# circuit.net
KiCad netlist of a schematic drawn in EAGLE
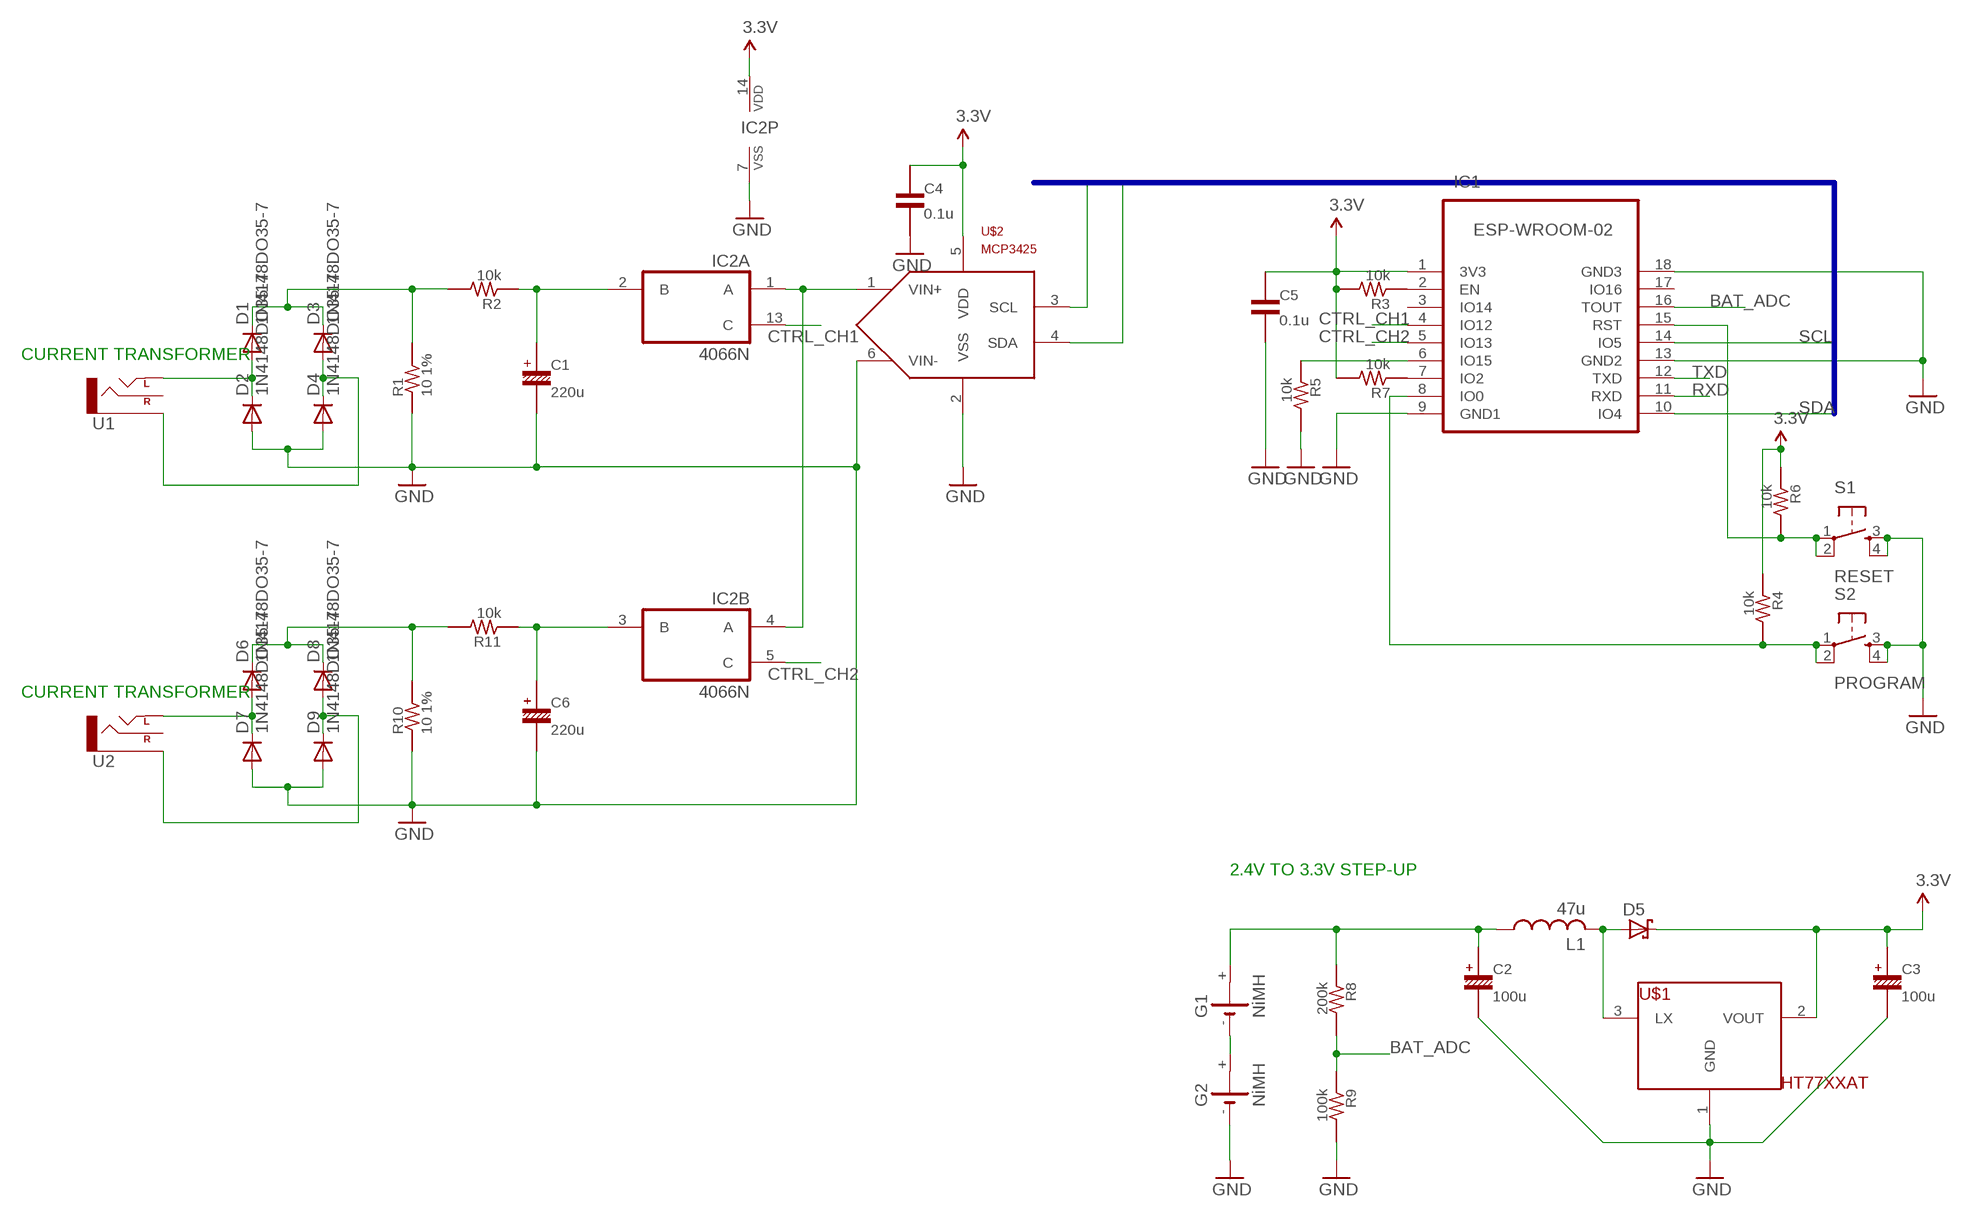
[diagram p0: schematic, sheet 1]

(export (version "E")
  (design (tool "Eeschema 10.0.6"))
  (components
    (comp (ref "C1")
      (value "220u")
      (footprint "eagle-import:16V-4-2.54")
      (libsource (lib "eagle-import") (part "CE-16V-04-2.54"))
    )
    (comp (ref "C2")
      (value "100u")
      (footprint "eagle-import:16V-6.3-5.08")
      (libsource (lib "eagle-import") (part "CE-16V-06.3-5.08"))
    )
    (comp (ref "C3")
      (value "100u")
      (footprint "eagle-import:16V-6.3-5.08")
      (libsource (lib "eagle-import") (part "CE-16V-06.3-5.08"))
    )
    (comp (ref "C4")
      (value "0.1u")
      (footprint "eagle-import:50-0302-2.54")
      (libsource (lib "eagle-import") (part "C-50V-0302-2.54"))
    )
    (comp (ref "C5")
      (value "0.1u")
      (footprint "eagle-import:50-0302-2.54")
      (libsource (lib "eagle-import") (part "C-50V-0302-2.54"))
    )
    (comp (ref "C6")
      (value "220u")
      (footprint "eagle-import:16V-4-2.54")
      (libsource (lib "eagle-import") (part "CE-16V-04-2.54"))
    )
    (comp (ref "D1")
      (value "1N4148DO35-7")
      (footprint "eagle-import:DO35-7")
      (libsource (lib "eagle-import") (part "1N4148DO35-7"))
    )
    (comp (ref "D2")
      (value "1N4148DO35-7")
      (footprint "eagle-import:DO35-7")
      (libsource (lib "eagle-import") (part "1N4148DO35-7"))
    )
    (comp (ref "D3")
      (value "1N4148DO35-7")
      (footprint "eagle-import:DO35-7")
      (libsource (lib "eagle-import") (part "1N4148DO35-7"))
    )
    (comp (ref "D4")
      (value "1N4148DO35-7")
      (footprint "eagle-import:DO35-7")
      (libsource (lib "eagle-import") (part "1N4148DO35-7"))
    )
    (comp (ref "D5")
      (value "SCHOTTKY-DIODEDO35-7")
      (footprint "eagle-import:DO35-7")
      (libsource (lib "eagle-import") (part "SCHOTTKY-DIODEDO35-7"))
    )
    (comp (ref "D6")
      (value "1N4148DO35-7")
      (footprint "eagle-import:DO35-7")
      (libsource (lib "eagle-import") (part "1N4148DO35-7"))
    )
    (comp (ref "D7")
      (value "1N4148DO35-7")
      (footprint "eagle-import:DO35-7")
      (libsource (lib "eagle-import") (part "1N4148DO35-7"))
    )
    (comp (ref "D8")
      (value "1N4148DO35-7")
      (footprint "eagle-import:DO35-7")
      (libsource (lib "eagle-import") (part "1N4148DO35-7"))
    )
    (comp (ref "D9")
      (value "1N4148DO35-7")
      (footprint "eagle-import:DO35-7")
      (libsource (lib "eagle-import") (part "1N4148DO35-7"))
    )
    (comp (ref "G1")
      (value "NiMH")
      (footprint "eagle-import:CRAA")
      (libsource (lib "eagle-import") (part "CRAA"))
    )
    (comp (ref "G2")
      (value "NiMH")
      (footprint "eagle-import:CRAA")
      (libsource (lib "eagle-import") (part "CRAA"))
    )
    (comp (ref "IC1")
      (value "ESP-WROOM-02")
      (footprint "eagle-import:ESP-WROOM-02")
      (libsource (lib "eagle-import") (part "ESP-WROOM-02"))
    )
    (comp (ref "IC2")
      (value "4066N")
      (footprint "eagle-import:DIL14")
      (libsource (lib "eagle-import") (part "4066N"))
    )
    (comp (ref "L1")
      (value "47u")
      (footprint "eagle-import:6000-XXXX-RC")
      (libsource (lib "eagle-import") (part "L-US6000-XXX-RC"))
    )
    (comp (ref "R1")
      (value "10 1%")
      (footprint "eagle-import:1_4W-7.62H")
      (libsource (lib "eagle-import") (part "R-1/4W-07.62"))
    )
    (comp (ref "R2")
      (value "10k")
      (footprint "eagle-import:1_4W-7.62H")
      (libsource (lib "eagle-import") (part "R-1/4W-07.62"))
    )
    (comp (ref "R3")
      (value "10k")
      (footprint "eagle-import:1_4W-7.62H")
      (libsource (lib "eagle-import") (part "R-1/4W-07.62"))
    )
    (comp (ref "R4")
      (value "10k")
      (footprint "eagle-import:1_4W-7.62H")
      (libsource (lib "eagle-import") (part "R-1/4W-07.62"))
    )
    (comp (ref "R5")
      (value "10k")
      (footprint "eagle-import:1_4W-7.62H")
      (libsource (lib "eagle-import") (part "R-1/4W-07.62"))
    )
    (comp (ref "R6")
      (value "10k")
      (footprint "eagle-import:1_4W-7.62H")
      (libsource (lib "eagle-import") (part "R-1/4W-07.62"))
    )
    (comp (ref "R7")
      (value "10k")
      (footprint "eagle-import:1_4W-7.62H")
      (libsource (lib "eagle-import") (part "R-1/4W-07.62"))
    )
    (comp (ref "R8")
      (value "200k")
      (footprint "eagle-import:1_4W-7.62H")
      (libsource (lib "eagle-import") (part "R-1/4W-07.62"))
    )
    (comp (ref "R9")
      (value "100k")
      (footprint "eagle-import:1_4W-7.62H")
      (libsource (lib "eagle-import") (part "R-1/4W-07.62"))
    )
    (comp (ref "R10")
      (value "10 1%")
      (footprint "eagle-import:1_4W-7.62H")
      (libsource (lib "eagle-import") (part "R-1/4W-07.62"))
    )
    (comp (ref "R11")
      (value "10k")
      (footprint "eagle-import:1_4W-7.62H")
      (libsource (lib "eagle-import") (part "R-1/4W-07.62"))
    )
    (comp (ref "S1")
      (value "RESET")
      (footprint "eagle-import:TACTILE-PTH")
      (libsource (lib "eagle-import") (part "TAC_SWITCHPTH"))
    )
    (comp (ref "S2")
      (value "PROGRAM")
      (footprint "eagle-import:TACTILE-PTH")
      (libsource (lib "eagle-import") (part "TAC_SWITCHPTH"))
    )
    (comp (ref "U$1")
      (value "HT77XXAT")
      (footprint "eagle-import:TO-92")
      (libsource (lib "eagle-import") (part "HT77XXAT"))
    )
    (comp (ref "U$2")
      (value "MCP3425")
      (footprint "eagle-import:SOT-23-6")
      (libsource (lib "eagle-import") (part "MCP3425"))
    )
    (comp (ref "U1")
      (value "AUDIO-JACK2.5MM")
      (footprint "eagle-import:STEREOJACK2.5MM_STEREOJACK2.5MM")
      (libsource (lib "eagle-import") (part "AUDIO-JACK2.5MM"))
    )
    (comp (ref "U2")
      (value "AUDIO-JACK2.5MM")
      (footprint "eagle-import:STEREOJACK2.5MM_STEREOJACK2.5MM")
      (libsource (lib "eagle-import") (part "AUDIO-JACK2.5MM"))
    )
  )
  (nets
    (net (code "1") (name "/BAT_ADC") (class "Default")
      (node (ref "IC1") (pin "16") (pinfunction "TOUT_16") (pintype "bidirectional"))
      (node (ref "R8") (pin "PAD2") (pinfunction "2_PAD2") (pintype "passive"))
      (node (ref "R9") (pin "PAD1") (pinfunction "1_PAD1") (pintype "passive"))
    )
    (net (code "2") (name "/CTRL_CH1") (class "Default")
      (node (ref "IC1") (pin "4") (pinfunction "IO12_4") (pintype "bidirectional"))
      (node (ref "IC2") (pin "13") (pinfunction "C_13") (pintype "input"))
    )
    (net (code "3") (name "/CTRL_CH2") (class "Default")
      (node (ref "IC1") (pin "5") (pinfunction "IO13_5") (pintype "bidirectional"))
      (node (ref "IC2") (pin "5") (pinfunction "C_5") (pintype "input"))
    )
    (net (code "4") (name "/RXD") (class "Default")
      (node (ref "IC1") (pin "11") (pinfunction "RXD_11") (pintype "bidirectional"))
    )
    (net (code "5") (name "/SCL") (class "Default")
      (node (ref "IC1") (pin "14") (pinfunction "IO5_14") (pintype "open_collector"))
      (node (ref "U$2") (pin "3") (pinfunction "SCL_3") (pintype "bidirectional"))
    )
    (net (code "6") (name "/SDA") (class "Default")
      (node (ref "IC1") (pin "10") (pinfunction "IO4_10") (pintype "bidirectional"))
      (node (ref "U$2") (pin "4") (pinfunction "SDA_4") (pintype "bidirectional"))
    )
    (net (code "7") (name "/TXD") (class "Default")
      (node (ref "IC1") (pin "12") (pinfunction "TXD_12") (pintype "bidirectional"))
    )
    (net (code "8") (name "3.3V") (class "Default")
      (node (ref "C3") (pin "+") (pinfunction "+_+") (pintype "passive"))
      (node (ref "C4") (pin "PAD1") (pinfunction "1_PAD1") (pintype "passive"))
      (node (ref "C5") (pin "PAD1") (pinfunction "1_PAD1") (pintype "passive"))
      (node (ref "D5") (pin "C") (pinfunction "C_C") (pintype "passive"))
      (node (ref "IC1") (pin "1") (pinfunction "3V3_1") (pintype "power_in"))
      (node (ref "IC2") (pin "14") (pinfunction "VDD_14") (pintype "power_in"))
      (node (ref "R3") (pin "PAD2") (pinfunction "2_PAD2") (pintype "passive"))
      (node (ref "R4") (pin "PAD1") (pinfunction "1_PAD1") (pintype "passive"))
      (node (ref "R6") (pin "PAD1") (pinfunction "1_PAD1") (pintype "passive"))
      (node (ref "R7") (pin "PAD2") (pinfunction "2_PAD2") (pintype "passive"))
      (node (ref "U$1") (pin "2") (pinfunction "VOUT_2") (pintype "power_in"))
      (node (ref "U$2") (pin "5") (pinfunction "VDD_5") (pintype "power_in"))
    )
    (net (code "9") (name "GND") (class "Default")
      (node (ref "C1") (pin "-") (pinfunction "-_-") (pintype "passive"))
      (node (ref "C2") (pin "-") (pinfunction "-_-") (pintype "passive"))
      (node (ref "C3") (pin "-") (pinfunction "-_-") (pintype "passive"))
      (node (ref "C4") (pin "PAD2") (pinfunction "2_PAD2") (pintype "passive"))
      (node (ref "C5") (pin "PAD2") (pinfunction "2_PAD2") (pintype "passive"))
      (node (ref "C6") (pin "-") (pinfunction "-_-") (pintype "passive"))
      (node (ref "D2") (pin "A") (pinfunction "A_A") (pintype "passive"))
      (node (ref "D4") (pin "A") (pinfunction "A_A") (pintype "passive"))
      (node (ref "D7") (pin "A") (pinfunction "A_A") (pintype "passive"))
      (node (ref "D9") (pin "A") (pinfunction "A_A") (pintype "passive"))
      (node (ref "G2") (pin "-") (pinfunction "-_-") (pintype "passive"))
      (node (ref "IC1") (pin "13") (pinfunction "GND2_13") (pintype "power_in"))
      (node (ref "IC1") (pin "18") (pinfunction "GND3_18") (pintype "power_in"))
      (node (ref "IC1") (pin "9") (pinfunction "GND1_9") (pintype "power_in"))
      (node (ref "IC2") (pin "7") (pinfunction "VSS_7") (pintype "power_in"))
      (node (ref "R1") (pin "PAD1") (pinfunction "1_PAD1") (pintype "passive"))
      (node (ref "R10") (pin "PAD1") (pinfunction "1_PAD1") (pintype "passive"))
      (node (ref "R5") (pin "PAD2") (pinfunction "2_PAD2") (pintype "passive"))
      (node (ref "R9") (pin "PAD2") (pinfunction "2_PAD2") (pintype "passive"))
      (node (ref "S1") (pin "3") (pinfunction "3_3") (pintype "passive"))
      (node (ref "S1") (pin "4") (pinfunction "4_4") (pintype "passive"))
      (node (ref "S2") (pin "3") (pinfunction "3_3") (pintype "passive"))
      (node (ref "S2") (pin "4") (pinfunction "4_4") (pintype "passive"))
      (node (ref "U$1") (pin "1") (pinfunction "GND_1") (pintype "power_in"))
      (node (ref "U$2") (pin "2") (pinfunction "VSS_2") (pintype "power_in"))
      (node (ref "U$2") (pin "6") (pinfunction "VIN-_6") (pintype "input"))
    )
    (net (code "10") (name "Net-(G1-Pad-)") (class "Default")
      (node (ref "G1") (pin "-") (pinfunction "-_-") (pintype "passive"))
      (node (ref "G2") (pin "+") (pinfunction "+_+") (pintype "passive"))
    )
    (net (code "11") (name "Net-(IC1-EN)") (class "Default")
      (node (ref "IC1") (pin "2") (pinfunction "EN_2") (pintype "bidirectional"))
      (node (ref "R3") (pin "PAD1") (pinfunction "1_PAD1") (pintype "passive"))
    )
    (net (code "12") (name "Net-(IC1-IO0)") (class "Default")
      (node (ref "IC1") (pin "8") (pinfunction "IO0_8") (pintype "bidirectional"))
      (node (ref "R4") (pin "PAD2") (pinfunction "2_PAD2") (pintype "passive"))
      (node (ref "S2") (pin "1") (pinfunction "1_1") (pintype "passive"))
      (node (ref "S2") (pin "2") (pinfunction "2_2") (pintype "passive"))
    )
    (net (code "13") (name "Net-(IC1-IO2)") (class "Default")
      (node (ref "IC1") (pin "7") (pinfunction "IO2_7") (pintype "bidirectional"))
      (node (ref "R7") (pin "PAD1") (pinfunction "1_PAD1") (pintype "passive"))
    )
    (net (code "14") (name "Net-(IC1-IO15)") (class "Default")
      (node (ref "IC1") (pin "6") (pinfunction "IO15_6") (pintype "bidirectional"))
      (node (ref "R5") (pin "PAD1") (pinfunction "1_PAD1") (pintype "passive"))
    )
    (net (code "15") (name "Net-(IC1-RST)") (class "Default")
      (node (ref "IC1") (pin "15") (pinfunction "RST_15") (pintype "bidirectional"))
      (node (ref "R6") (pin "PAD2") (pinfunction "2_PAD2") (pintype "passive"))
      (node (ref "S1") (pin "1") (pinfunction "1_1") (pintype "passive"))
      (node (ref "S1") (pin "2") (pinfunction "2_2") (pintype "passive"))
    )
    (net (code "16") (name "Net-(IC2A-A)") (class "Default")
      (node (ref "IC2") (pin "1") (pinfunction "A_1") (pintype "tri_state"))
      (node (ref "IC2") (pin "4") (pinfunction "A_4") (pintype "tri_state"))
      (node (ref "U$2") (pin "1") (pinfunction "VIN+_1") (pintype "input"))
    )
    (net (code "17") (name "Net-(IC2A-B)") (class "Default")
      (node (ref "C1") (pin "+") (pinfunction "+_+") (pintype "passive"))
      (node (ref "IC2") (pin "2") (pinfunction "B_2") (pintype "tri_state"))
      (node (ref "R2") (pin "PAD1") (pinfunction "1_PAD1") (pintype "passive"))
    )
    (net (code "18") (name "Net-(IC2B-B)") (class "Default")
      (node (ref "C6") (pin "+") (pinfunction "+_+") (pintype "passive"))
      (node (ref "IC2") (pin "3") (pinfunction "B_3") (pintype "tri_state"))
      (node (ref "R11") (pin "PAD1") (pinfunction "1_PAD1") (pintype "passive"))
    )
    (net (code "19") (name "Net-(R1-2)") (class "Default")
      (node (ref "D1") (pin "C") (pinfunction "C_C") (pintype "passive"))
      (node (ref "D3") (pin "C") (pinfunction "C_C") (pintype "passive"))
      (node (ref "R1") (pin "PAD2") (pinfunction "2_PAD2") (pintype "passive"))
      (node (ref "R2") (pin "PAD2") (pinfunction "2_PAD2") (pintype "passive"))
    )
    (net (code "20") (name "Net-(R8-1)") (class "Default")
      (node (ref "C2") (pin "+") (pinfunction "+_+") (pintype "passive"))
      (node (ref "G1") (pin "+") (pinfunction "+_+") (pintype "passive"))
      (node (ref "L1") (pin "1") (pinfunction "1_1") (pintype "passive"))
      (node (ref "R8") (pin "PAD1") (pinfunction "1_PAD1") (pintype "passive"))
    )
    (net (code "21") (name "Net-(R10-2)") (class "Default")
      (node (ref "D6") (pin "C") (pinfunction "C_C") (pintype "passive"))
      (node (ref "D8") (pin "C") (pinfunction "C_C") (pintype "passive"))
      (node (ref "R10") (pin "PAD2") (pinfunction "2_PAD2") (pintype "passive"))
      (node (ref "R11") (pin "PAD2") (pinfunction "2_PAD2") (pintype "passive"))
    )
    (net (code "22") (name "Net-(U$1-LX)") (class "Default")
      (node (ref "D5") (pin "A") (pinfunction "A_A") (pintype "passive"))
      (node (ref "L1") (pin "2") (pinfunction "2_2") (pintype "passive"))
      (node (ref "U$1") (pin "3") (pinfunction "LX_3") (pintype "power_in"))
    )
    (net (code "23") (name "Net-(U1-LEFT)") (class "Default")
      (node (ref "D1") (pin "A") (pinfunction "A_A") (pintype "passive"))
      (node (ref "D2") (pin "C") (pinfunction "C_C") (pintype "passive"))
      (node (ref "U1") (pin "SHIELD") (pinfunction "LEFT_SHIELD") (pintype "bidirectional"))
    )
    (net (code "24") (name "Net-(U1-SLEEVE)") (class "Default")
      (node (ref "D3") (pin "A") (pinfunction "A_A") (pintype "passive"))
      (node (ref "D4") (pin "C") (pinfunction "C_C") (pintype "passive"))
      (node (ref "U1") (pin "RING1") (pinfunction "SLEEVE_RING1") (pintype "bidirectional"))
    )
    (net (code "25") (name "Net-(U2-LEFT)") (class "Default")
      (node (ref "D6") (pin "A") (pinfunction "A_A") (pintype "passive"))
      (node (ref "D7") (pin "C") (pinfunction "C_C") (pintype "passive"))
      (node (ref "U2") (pin "SHIELD") (pinfunction "LEFT_SHIELD") (pintype "bidirectional"))
    )
    (net (code "26") (name "Net-(U2-SLEEVE)") (class "Default")
      (node (ref "D8") (pin "A") (pinfunction "A_A") (pintype "passive"))
      (node (ref "D9") (pin "C") (pinfunction "C_C") (pintype "passive"))
      (node (ref "U2") (pin "RING1") (pinfunction "SLEEVE_RING1") (pintype "bidirectional"))
    )
    (net (code "27") (name "unconnected-(G1-+-Pad+@1)") (class "Default")
      (node (ref "G1") (pin "+@1") (pinfunction "+_+@1") (pintype "passive"))
    )
    (net (code "28") (name "unconnected-(G2-+-Pad+@1)") (class "Default")
      (node (ref "G2") (pin "+@1") (pinfunction "+_+@1") (pintype "passive"))
    )
    (net (code "29") (name "unconnected-(IC1-IO14-Pad3)") (class "Default")
      (node (ref "IC1") (pin "3") (pinfunction "IO14_3") (pintype "bidirectional"))
    )
    (net (code "30") (name "unconnected-(IC1-IO16-Pad17)") (class "Default")
      (node (ref "IC1") (pin "17") (pinfunction "IO16_17") (pintype "bidirectional"))
    )
    (net (code "31") (name "unconnected-(U1-RIGHT-PadTIP)") (class "Default")
      (node (ref "U1") (pin "TIP") (pinfunction "RIGHT_TIP") (pintype "bidirectional"))
    )
    (net (code "32") (name "unconnected-(U2-RIGHT-PadTIP)") (class "Default")
      (node (ref "U2") (pin "TIP") (pinfunction "RIGHT_TIP") (pintype "bidirectional"))
    )
  )
)
